# Schematic.net
KiCad netlist of a schematic drawn in Altium Designer
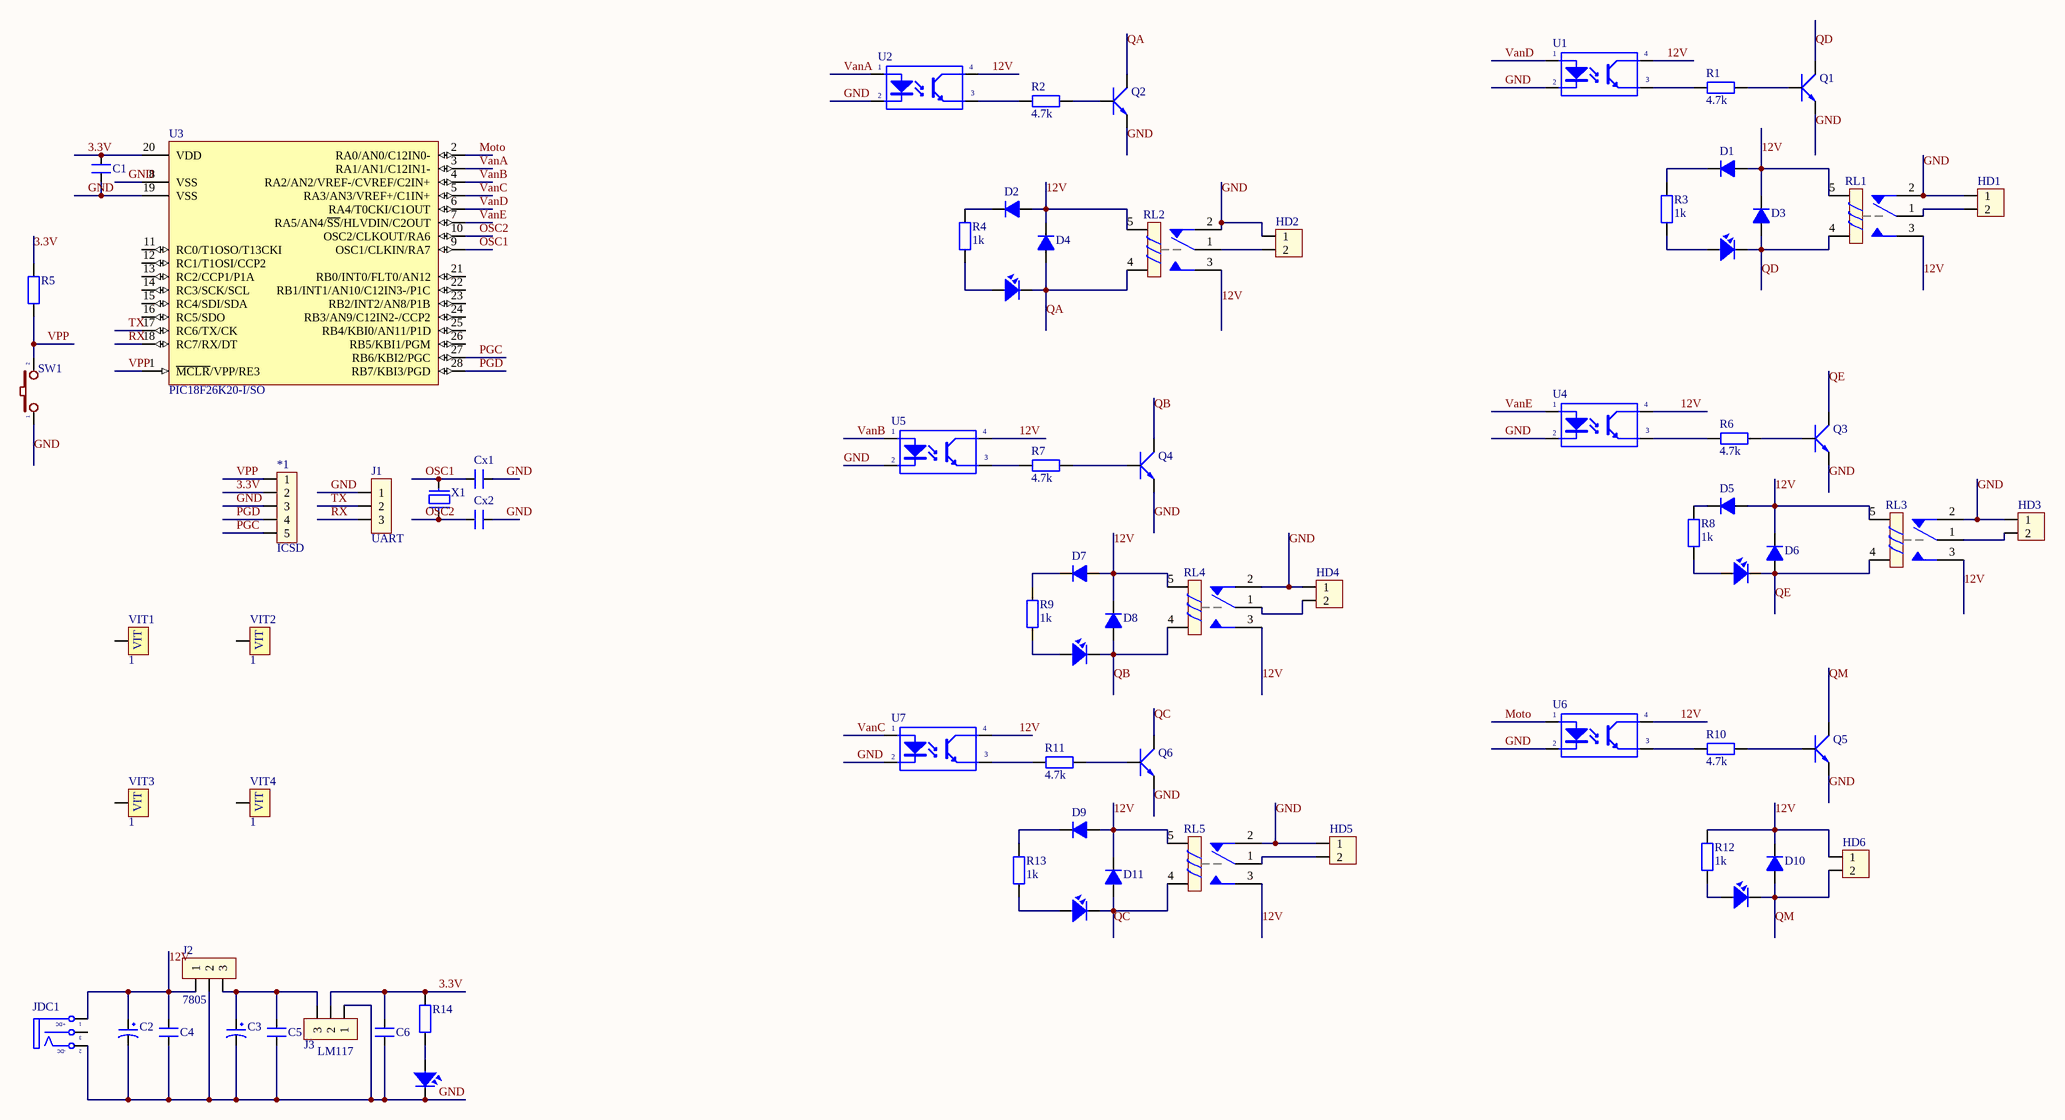
[diagram p0: Schematic.SchDoc]

(export (version "E")
  (design (tool "Eeschema 10.0.6"))
  (components
    (comp (ref "*1") (value "ICSD") (footprint "CON5") (libsource (lib "syhaunguyen") (part "JP5")))
    (comp (ref "C1")
      (value "104")
      (footprint "CN2")
      (description "Cap np Cremic Value  104pF => 105pF")
      (libsource (lib "syhaunguyen") (part "CN2"))
    )
    (comp (ref "C2")
      (value "100uF/35V")
      (footprint "CP1.5/3.4")
      (description "Cap 100uF/35V - 470uF/16V")
      (libsource (lib "syhaunguyen") (part "CP3"))
    )
    (comp (ref "C3")
      (value "10uF")
      (footprint "CP1/2")
      (description "Cap P  0,1uF < 22uF , 16 - 50V")
      (libsource (lib "syhaunguyen") (part "CP1"))
    )
    (comp (ref "C4")
      (value "104")
      (footprint "CN2")
      (description "Cap np Cremic Value  104pF => 105pF")
      (libsource (lib "syhaunguyen") (part "CN2"))
    )
    (comp (ref "C5")
      (value "104")
      (footprint "CN2")
      (description "Cap np Cremic Value  104pF => 105pF")
      (libsource (lib "syhaunguyen") (part "CN2"))
    )
    (comp (ref "C6")
      (value "104")
      (footprint "CN2")
      (description "Cap np Cremic Value  104pF => 105pF")
      (libsource (lib "syhaunguyen") (part "CN2"))
    )
    (comp (ref "Cx1")
      (value "33pF")
      (footprint "CN1")
      (description "Cap np Cremic value 1pF => 100pF")
      (libsource (lib "syhaunguyen") (part "CN0"))
    )
    (comp (ref "Cx2")
      (value "33pF")
      (footprint "CN1")
      (description "Cap np Cremic value 1pF => 100pF")
      (libsource (lib "syhaunguyen") (part "CN0"))
    )
    (comp (ref "D1")
      (value "1N4007")
      (footprint "D1A")
      (description "Diode 1A")
      (libsource (lib "syhaunguyen") (part "D1A"))
    )
    (comp (ref "D2")
      (value "1N4007")
      (footprint "D1A")
      (description "Diode 1A")
      (libsource (lib "syhaunguyen") (part "D1A"))
    )
    (comp (ref "D3")
      (value "1N4007")
      (footprint "D1A")
      (description "Diode 1A")
      (libsource (lib "syhaunguyen") (part "D1A"))
    )
    (comp (ref "D4")
      (value "1N4007")
      (footprint "D1A")
      (description "Diode 1A")
      (libsource (lib "syhaunguyen") (part "D1A"))
    )
    (comp (ref "D5")
      (value "1N4007")
      (footprint "D1A")
      (description "Diode 1A")
      (libsource (lib "syhaunguyen") (part "D1A"))
    )
    (comp (ref "D6")
      (value "1N4007")
      (footprint "D1A")
      (description "Diode 1A")
      (libsource (lib "syhaunguyen") (part "D1A"))
    )
    (comp (ref "D7")
      (value "1N4007")
      (footprint "D1A")
      (description "Diode 1A")
      (libsource (lib "syhaunguyen") (part "D1A"))
    )
    (comp (ref "D8")
      (value "1N4007")
      (footprint "D1A")
      (description "Diode 1A")
      (libsource (lib "syhaunguyen") (part "D1A"))
    )
    (comp (ref "D9")
      (value "1N4007")
      (footprint "D1A")
      (description "Diode 1A")
      (libsource (lib "syhaunguyen") (part "D1A"))
    )
    (comp (ref "D10")
      (value "1N4007")
      (footprint "D1A")
      (description "Diode 1A")
      (libsource (lib "syhaunguyen") (part "D1A"))
    )
    (comp (ref "D11")
      (value "1N4007")
      (footprint "D1A")
      (description "Diode 1A")
      (libsource (lib "syhaunguyen") (part "D1A"))
    )
    (comp (ref "HD1")
      (value "Header 2")
      (footprint "CON2")
      (description "Header 2 (Green)")
      (libsource (lib "syhaunguyen") (part "Hed2"))
    )
    (comp (ref "HD2")
      (value "Header 2")
      (footprint "CON2")
      (description "Header 2 (Green)")
      (libsource (lib "syhaunguyen") (part "Hed2"))
    )
    (comp (ref "HD3")
      (value "Header 2")
      (footprint "CON2")
      (description "Header 2 (Green)")
      (libsource (lib "syhaunguyen") (part "Hed2"))
    )
    (comp (ref "HD4")
      (value "Header 2")
      (footprint "CON2")
      (description "Header 2 (Green)")
      (libsource (lib "syhaunguyen") (part "Hed2"))
    )
    (comp (ref "HD5")
      (value "Header 2")
      (footprint "CON2")
      (description "Header 2 (Green)")
      (libsource (lib "syhaunguyen") (part "Hed2"))
    )
    (comp (ref "HD6")
      (value "Header 2")
      (footprint "CON2")
      (description "Header 2 (Green)")
      (libsource (lib "syhaunguyen") (part "Hed2"))
    )
    (comp (ref "J1")
      (value "UART")
      (footprint "CON3")
      (description "Jumper 3")
      (libsource (lib "") (part "JP3_1"))
    )
    (comp (ref "J2")
      (value "7805")
      (footprint "QTO-220H3")
      (description "Jumper 3")
      (libsource (lib "") (part "JP3_2"))
    )
    (comp (ref "J3")
      (value "LM117")
      (footprint "QTO-220H3")
      (description "Jumper 3")
      (libsource (lib "syhaunguyen") (part "JP3"))
    )
    (comp (ref "JDC1")
      (value "Jac DC")
      (footprint "DC-IN")
      (description "Jac DC input")
      (libsource (lib "syhaunguyen") (part "DCIN"))
    )
    (comp (ref "LED1")
      (value "LED")
      (footprint "LED-5TRED")
      (description "Led  Vuong")
      (libsource (lib "syhaunguyen") (part "LED"))
    )
    (comp (ref "LED2")
      (value "LED")
      (footprint "LED-5TRED")
      (description "Led  Vuong")
      (libsource (lib "syhaunguyen") (part "LED"))
    )
    (comp (ref "LED3")
      (value "LED")
      (footprint "LED-5TRED")
      (description "Led  Vuong")
      (libsource (lib "syhaunguyen") (part "LED"))
    )
    (comp (ref "LED4")
      (value "LED")
      (footprint "LED-5TRED")
      (description "Led  Vuong")
      (libsource (lib "syhaunguyen") (part "LED"))
    )
    (comp (ref "LED5")
      (value "LED")
      (footprint "LED-5TRED")
      (description "Led  Vuong")
      (libsource (lib "syhaunguyen") (part "LED"))
    )
    (comp (ref "LED6")
      (value "LED")
      (footprint "LED-5TRED")
      (description "Led  Vuong")
      (libsource (lib "syhaunguyen") (part "LED"))
    )
    (comp (ref "LED7")
      (value "LED")
      (footprint "LED-5TRED")
      (description "Led  Vuong")
      (libsource (lib "syhaunguyen") (part "LED"))
    )
    (comp (ref "Q1")
      (value "C1815")
      (footprint "QTO-92")
      (description "NPN 600mW, ECB")
      (libsource (lib "syhaunguyen") (part "C1815"))
    )
    (comp (ref "Q2")
      (value "C1815")
      (footprint "QTO-92")
      (description "NPN 600mW, ECB")
      (libsource (lib "syhaunguyen") (part "C1815"))
    )
    (comp (ref "Q3")
      (value "C1815")
      (footprint "QTO-92")
      (description "NPN 600mW, ECB")
      (libsource (lib "syhaunguyen") (part "C1815"))
    )
    (comp (ref "Q4")
      (value "C1815")
      (footprint "QTO-92")
      (description "NPN 600mW, ECB")
      (libsource (lib "syhaunguyen") (part "C1815"))
    )
    (comp (ref "Q5")
      (value "C1815")
      (footprint "QTO-92")
      (description "NPN 600mW, ECB")
      (libsource (lib "syhaunguyen") (part "C1815"))
    )
    (comp (ref "Q6")
      (value "C1815")
      (footprint "QTO-92")
      (description "NPN 600mW, ECB")
      (libsource (lib "syhaunguyen") (part "C1815"))
    )
    (comp (ref "R1")
      (value "4.7k")
      (footprint "R1/4W")
      (description "Resistor 1/4W")
      (libsource (lib "syhaunguyen") (part "R1/4W"))
    )
    (comp (ref "R2")
      (value "4.7k")
      (footprint "R1/4W")
      (description "Resistor 1/4W")
      (libsource (lib "syhaunguyen") (part "R1/4W"))
    )
    (comp (ref "R3")
      (value "1k")
      (footprint "R1/4W")
      (description "Resistor 1/4W")
      (libsource (lib "syhaunguyen") (part "R1/4W"))
    )
    (comp (ref "R4")
      (value "1k")
      (footprint "R1/4W")
      (description "Resistor 1/4W")
      (libsource (lib "syhaunguyen") (part "R1/4W"))
    )
    (comp (ref "R5")
      (value "1k")
      (footprint "R1/4W")
      (description "Resistor 1/4W")
      (libsource (lib "syhaunguyen") (part "R1/4W"))
    )
    (comp (ref "R6")
      (value "4.7k")
      (footprint "R1/4W")
      (description "Resistor 1/4W")
      (libsource (lib "syhaunguyen") (part "R1/4W"))
    )
    (comp (ref "R7")
      (value "4.7k")
      (footprint "R1/4W")
      (description "Resistor 1/4W")
      (libsource (lib "syhaunguyen") (part "R1/4W"))
    )
    (comp (ref "R8")
      (value "1k")
      (footprint "R1/4W")
      (description "Resistor 1/4W")
      (libsource (lib "syhaunguyen") (part "R1/4W"))
    )
    (comp (ref "R9")
      (value "1k")
      (footprint "R1/4W")
      (description "Resistor 1/4W")
      (libsource (lib "syhaunguyen") (part "R1/4W"))
    )
    (comp (ref "R10")
      (value "4.7k")
      (footprint "R1/4W")
      (description "Resistor 1/4W")
      (libsource (lib "syhaunguyen") (part "R1/4W"))
    )
    (comp (ref "R11")
      (value "4.7k")
      (footprint "R1/4W")
      (description "Resistor 1/4W")
      (libsource (lib "syhaunguyen") (part "R1/4W"))
    )
    (comp (ref "R12")
      (value "1k")
      (footprint "R1/4W")
      (description "Resistor 1/4W")
      (libsource (lib "syhaunguyen") (part "R1/4W"))
    )
    (comp (ref "R13")
      (value "1k")
      (footprint "R1/4W")
      (description "Resistor 1/4W")
      (libsource (lib "syhaunguyen") (part "R1/4W"))
    )
    (comp (ref "R14")
      (value "1k")
      (footprint "R1/4W")
      (description "Resistor 1/4W")
      (libsource (lib "syhaunguyen") (part "R1/4W"))
    )
    (comp (ref "RL1")
      (value "Relay 10A/12V")
      (footprint "RL_SPDT_10A")
      (description "Relay SPDT,10A - 12VDC 5 Pin")
      (libsource (lib "syhaunguyen") (part "Relay 1"))
    )
    (comp (ref "RL2")
      (value "Relay 10A/12V")
      (footprint "RL_SPDT_10A")
      (description "Relay SPDT,10A - 12VDC 5 Pin")
      (libsource (lib "syhaunguyen") (part "Relay 1"))
    )
    (comp (ref "RL3")
      (value "Relay 10A/12V")
      (footprint "RL_SPDT_10A")
      (description "Relay SPDT,10A - 12VDC 5 Pin")
      (libsource (lib "syhaunguyen") (part "Relay 1"))
    )
    (comp (ref "RL4")
      (value "Relay 10A/12V")
      (footprint "RL_SPDT_10A")
      (description "Relay SPDT,10A - 12VDC 5 Pin")
      (libsource (lib "syhaunguyen") (part "Relay 1"))
    )
    (comp (ref "RL5")
      (value "Relay 10A/12V")
      (footprint "RL_SPDT_10A")
      (description "Relay SPDT,10A - 12VDC 5 Pin")
      (libsource (lib "syhaunguyen") (part "Relay 1"))
    )
    (comp (ref "SW1")
      (value "SW")
      (footprint "SW2")
      (description "Switch button 2 pin")
      (libsource (lib "syhaunguyen") (part "SW2"))
    )
    (comp (ref "U1")
      (value "PC817")
      (footprint "DIP4/W0.3")
      (description "Single Opto")
      (libsource (lib "syhaunguyen") (part "PC817"))
    )
    (comp (ref "U2")
      (value "PC817")
      (footprint "DIP4/W0.3")
      (description "Single Opto")
      (libsource (lib "syhaunguyen") (part "PC817"))
    )
    (comp (ref "U3")
      (value "PIC18F26K20-I/SO")
      (footprint "SOIC-SO28_N")
      (fields (field (name "PUBLISHER") "Altium Limited"))
      (libsource (lib "Microchip Microcontroller 8-Bit PIC18") (part "PIC18F26K20-I/SO"))
    )
    (comp (ref "U4")
      (value "PC817")
      (footprint "DIP4/W0.3")
      (description "Single Opto")
      (libsource (lib "syhaunguyen") (part "PC817"))
    )
    (comp (ref "U5")
      (value "PC817")
      (footprint "DIP4/W0.3")
      (description "Single Opto")
      (libsource (lib "syhaunguyen") (part "PC817"))
    )
    (comp (ref "U6")
      (value "PC817")
      (footprint "DIP4/W0.3")
      (description "Single Opto")
      (libsource (lib "syhaunguyen") (part "PC817"))
    )
    (comp (ref "U7")
      (value "PC817")
      (footprint "DIP4/W0.3")
      (description "Single Opto")
      (libsource (lib "syhaunguyen") (part "PC817"))
    )
    (comp (ref "VIT1")
      (value "1")
      (footprint "VIT")
      (description "Oc Vit")
      (libsource (lib "syhaunguyen") (part "VIT"))
    )
    (comp (ref "VIT2")
      (value "1")
      (footprint "VIT")
      (description "Oc Vit")
      (libsource (lib "syhaunguyen") (part "VIT"))
    )
    (comp (ref "VIT3")
      (value "1")
      (footprint "VIT")
      (description "Oc Vit")
      (libsource (lib "syhaunguyen") (part "VIT"))
    )
    (comp (ref "VIT4")
      (value "1")
      (footprint "VIT")
      (description "Oc Vit")
      (libsource (lib "syhaunguyen") (part "VIT"))
    )
    (comp (ref "X1")
      (value "4Mhz")
      (footprint "XT2")
      (description "Crystal For all Crystal 2pin.")
      (libsource (lib "syhaunguyen") (part "XT2"))
    )
  )
  (nets
    (net (code "1") (name "/3.3V") (class "Default")
      (node (ref "*1") (pin "2") (pinfunction "2_2") (pintype "passive"))
      (node (ref "C1") (pin "2") (pinfunction "2_2") (pintype "passive"))
      (node (ref "C6") (pin "1") (pinfunction "1_1") (pintype "passive"))
      (node (ref "J3") (pin "2") (pinfunction "2_2") (pintype "passive"))
      (node (ref "R14") (pin "2") (pinfunction "2_2") (pintype "passive"))
      (node (ref "R5") (pin "2") (pinfunction "2_2") (pintype "passive"))
      (node (ref "U3") (pin "20") (pinfunction "VDD_20") (pintype "power_in"))
    )
    (net (code "2") (name "/12V") (class "Default")
      (node (ref "C2") (pin "1") (pinfunction "1_1") (pintype "passive"))
      (node (ref "C4") (pin "1") (pinfunction "1_1") (pintype "passive"))
      (node (ref "D1") (pin "1") (pinfunction "A_1") (pintype "passive"))
      (node (ref "D10") (pin "2") (pinfunction "K_2") (pintype "passive"))
      (node (ref "D11") (pin "2") (pinfunction "K_2") (pintype "passive"))
      (node (ref "D2") (pin "1") (pinfunction "A_1") (pintype "passive"))
      (node (ref "D3") (pin "2") (pinfunction "K_2") (pintype "passive"))
      (node (ref "D4") (pin "2") (pinfunction "K_2") (pintype "passive"))
      (node (ref "D5") (pin "1") (pinfunction "A_1") (pintype "passive"))
      (node (ref "D6") (pin "2") (pinfunction "K_2") (pintype "passive"))
      (node (ref "D7") (pin "1") (pinfunction "A_1") (pintype "passive"))
      (node (ref "D8") (pin "2") (pinfunction "K_2") (pintype "passive"))
      (node (ref "D9") (pin "1") (pinfunction "A_1") (pintype "passive"))
      (node (ref "HD6") (pin "1") (pinfunction "1_1") (pintype "passive"))
      (node (ref "J2") (pin "1") (pinfunction "1_1") (pintype "passive"))
      (node (ref "JDC1") (pin "1") (pinfunction "T_1") (pintype "passive"))
      (node (ref "R12") (pin "2") (pinfunction "2_2") (pintype "passive"))
      (node (ref "RL1") (pin "3") (pinfunction "3_3") (pintype "passive"))
      (node (ref "RL1") (pin "5") (pinfunction "5_5") (pintype "passive"))
      (node (ref "RL2") (pin "3") (pinfunction "3_3") (pintype "passive"))
      (node (ref "RL2") (pin "5") (pinfunction "5_5") (pintype "passive"))
      (node (ref "RL3") (pin "3") (pinfunction "3_3") (pintype "passive"))
      (node (ref "RL3") (pin "5") (pinfunction "5_5") (pintype "passive"))
      (node (ref "RL4") (pin "3") (pinfunction "3_3") (pintype "passive"))
      (node (ref "RL4") (pin "5") (pinfunction "5_5") (pintype "passive"))
      (node (ref "RL5") (pin "3") (pinfunction "3_3") (pintype "passive"))
      (node (ref "RL5") (pin "5") (pinfunction "5_5") (pintype "passive"))
      (node (ref "U1") (pin "4") (pinfunction "C_4") (pintype "passive"))
      (node (ref "U2") (pin "4") (pinfunction "C_4") (pintype "passive"))
      (node (ref "U4") (pin "4") (pinfunction "C_4") (pintype "passive"))
      (node (ref "U5") (pin "4") (pinfunction "C_4") (pintype "passive"))
      (node (ref "U6") (pin "4") (pinfunction "C_4") (pintype "passive"))
      (node (ref "U7") (pin "4") (pinfunction "C_4") (pintype "passive"))
    )
    (net (code "3") (name "/GND") (class "Default")
      (node (ref "*1") (pin "3") (pinfunction "3_3") (pintype "passive"))
      (node (ref "C1") (pin "1") (pinfunction "1_1") (pintype "passive"))
      (node (ref "C2") (pin "2") (pinfunction "2_2") (pintype "passive"))
      (node (ref "C3") (pin "2") (pinfunction "2_2") (pintype "passive"))
      (node (ref "C4") (pin "2") (pinfunction "2_2") (pintype "passive"))
      (node (ref "C5") (pin "2") (pinfunction "2_2") (pintype "passive"))
      (node (ref "C6") (pin "2") (pinfunction "2_2") (pintype "passive"))
      (node (ref "Cx1") (pin "2") (pinfunction "2_2") (pintype "passive"))
      (node (ref "Cx2") (pin "2") (pinfunction "2_2") (pintype "passive"))
      (node (ref "HD1") (pin "1") (pinfunction "1_1") (pintype "passive"))
      (node (ref "HD2") (pin "1") (pinfunction "1_1") (pintype "passive"))
      (node (ref "HD3") (pin "1") (pinfunction "1_1") (pintype "passive"))
      (node (ref "HD4") (pin "1") (pinfunction "1_1") (pintype "passive"))
      (node (ref "HD5") (pin "1") (pinfunction "1_1") (pintype "passive"))
      (node (ref "J1") (pin "1") (pinfunction "1_1") (pintype "passive"))
      (node (ref "J2") (pin "2") (pinfunction "2_2") (pintype "passive"))
      (node (ref "J3") (pin "1") (pinfunction "1_1") (pintype "passive"))
      (node (ref "JDC1") (pin "2") (pinfunction "TN_2") (pintype "passive"))
      (node (ref "LED7") (pin "2") (pinfunction "2_2") (pintype "passive"))
      (node (ref "Q1") (pin "1") (pinfunction "E_1") (pintype "passive"))
      (node (ref "Q2") (pin "1") (pinfunction "E_1") (pintype "passive"))
      (node (ref "Q3") (pin "1") (pinfunction "E_1") (pintype "passive"))
      (node (ref "Q4") (pin "1") (pinfunction "E_1") (pintype "passive"))
      (node (ref "Q5") (pin "1") (pinfunction "E_1") (pintype "passive"))
      (node (ref "Q6") (pin "1") (pinfunction "E_1") (pintype "passive"))
      (node (ref "RL1") (pin "2") (pinfunction "2_2") (pintype "passive"))
      (node (ref "RL2") (pin "2") (pinfunction "2_2") (pintype "passive"))
      (node (ref "RL3") (pin "2") (pinfunction "2_2") (pintype "passive"))
      (node (ref "RL4") (pin "2") (pinfunction "2_2") (pintype "passive"))
      (node (ref "RL5") (pin "2") (pinfunction "2_2") (pintype "passive"))
      (node (ref "SW1") (pin "1") (pinfunction "1_1") (pintype "passive"))
      (node (ref "U1") (pin "2") (pinfunction "K_2") (pintype "passive"))
      (node (ref "U2") (pin "2") (pinfunction "K_2") (pintype "passive"))
      (node (ref "U3") (pin "19") (pinfunction "VSS_19") (pintype "power_in"))
      (node (ref "U3") (pin "8") (pinfunction "VSS_8") (pintype "power_in"))
      (node (ref "U4") (pin "2") (pinfunction "K_2") (pintype "passive"))
      (node (ref "U5") (pin "2") (pinfunction "K_2") (pintype "passive"))
      (node (ref "U6") (pin "2") (pinfunction "K_2") (pintype "passive"))
      (node (ref "U7") (pin "2") (pinfunction "K_2") (pintype "passive"))
    )
    (net (code "4") (name "/Moto") (class "Default")
      (node (ref "U3") (pin "2") (pinfunction "RA0/AN0/C12IN0-_2") (pintype "bidirectional"))
      (node (ref "U6") (pin "1") (pinfunction "A_1") (pintype "passive"))
    )
    (net (code "5") (name "/OSC1") (class "Default")
      (node (ref "Cx1") (pin "1") (pinfunction "1_1") (pintype "passive"))
      (node (ref "U3") (pin "9") (pinfunction "OSC1/CLKIN/RA7_9") (pintype "bidirectional"))
      (node (ref "X1") (pin "2") (pinfunction "2_2") (pintype "passive"))
    )
    (net (code "6") (name "/OSC2") (class "Default")
      (node (ref "Cx2") (pin "1") (pinfunction "1_1") (pintype "passive"))
      (node (ref "U3") (pin "10") (pinfunction "OSC2/CLKOUT/RA6_10") (pintype "bidirectional"))
      (node (ref "X1") (pin "1") (pinfunction "1_1") (pintype "passive"))
    )
    (net (code "7") (name "/PGC") (class "Default")
      (node (ref "*1") (pin "5") (pinfunction "5_5") (pintype "passive"))
      (node (ref "U3") (pin "27") (pinfunction "RB6/KBI2/PGC_27") (pintype "bidirectional"))
    )
    (net (code "8") (name "/PGD") (class "Default")
      (node (ref "*1") (pin "4") (pinfunction "4_4") (pintype "passive"))
      (node (ref "U3") (pin "28") (pinfunction "RB7/KBI3/PGD_28") (pintype "bidirectional"))
    )
    (net (code "9") (name "/QA") (class "Default")
      (node (ref "D4") (pin "1") (pinfunction "A_1") (pintype "passive"))
      (node (ref "LED2") (pin "2") (pinfunction "2_2") (pintype "passive"))
      (node (ref "Q2") (pin "2") (pinfunction "C_2") (pintype "passive"))
      (node (ref "RL2") (pin "4") (pinfunction "4_4") (pintype "passive"))
    )
    (net (code "10") (name "/QB") (class "Default")
      (node (ref "D8") (pin "1") (pinfunction "A_1") (pintype "passive"))
      (node (ref "LED4") (pin "2") (pinfunction "2_2") (pintype "passive"))
      (node (ref "Q4") (pin "2") (pinfunction "C_2") (pintype "passive"))
      (node (ref "RL4") (pin "4") (pinfunction "4_4") (pintype "passive"))
    )
    (net (code "11") (name "/QC") (class "Default")
      (node (ref "D11") (pin "1") (pinfunction "A_1") (pintype "passive"))
      (node (ref "LED6") (pin "2") (pinfunction "2_2") (pintype "passive"))
      (node (ref "Q6") (pin "2") (pinfunction "C_2") (pintype "passive"))
      (node (ref "RL5") (pin "4") (pinfunction "4_4") (pintype "passive"))
    )
    (net (code "12") (name "/QD") (class "Default")
      (node (ref "D3") (pin "1") (pinfunction "A_1") (pintype "passive"))
      (node (ref "LED1") (pin "2") (pinfunction "2_2") (pintype "passive"))
      (node (ref "Q1") (pin "2") (pinfunction "C_2") (pintype "passive"))
      (node (ref "RL1") (pin "4") (pinfunction "4_4") (pintype "passive"))
    )
    (net (code "13") (name "/QE") (class "Default")
      (node (ref "D6") (pin "1") (pinfunction "A_1") (pintype "passive"))
      (node (ref "LED3") (pin "2") (pinfunction "2_2") (pintype "passive"))
      (node (ref "Q3") (pin "2") (pinfunction "C_2") (pintype "passive"))
      (node (ref "RL3") (pin "4") (pinfunction "4_4") (pintype "passive"))
    )
    (net (code "14") (name "/QM") (class "Default")
      (node (ref "D10") (pin "1") (pinfunction "A_1") (pintype "passive"))
      (node (ref "HD6") (pin "2") (pinfunction "2_2") (pintype "passive"))
      (node (ref "LED5") (pin "2") (pinfunction "2_2") (pintype "passive"))
      (node (ref "Q5") (pin "2") (pinfunction "C_2") (pintype "passive"))
    )
    (net (code "15") (name "/RX") (class "Default")
      (node (ref "J1") (pin "3") (pinfunction "3_3") (pintype "passive"))
      (node (ref "U3") (pin "18") (pinfunction "RC7/RX/DT_18") (pintype "bidirectional"))
    )
    (net (code "16") (name "/TX") (class "Default")
      (node (ref "J1") (pin "2") (pinfunction "2_2") (pintype "passive"))
      (node (ref "U3") (pin "17") (pinfunction "RC6/TX/CK_17") (pintype "bidirectional"))
    )
    (net (code "17") (name "/VPP") (class "Default")
      (node (ref "*1") (pin "1") (pinfunction "1_1") (pintype "passive"))
      (node (ref "R5") (pin "1") (pinfunction "1_1") (pintype "passive"))
      (node (ref "SW1") (pin "2") (pinfunction "2_2") (pintype "passive"))
      (node (ref "U3") (pin "1") (pinfunction "~{MCLR}/VPP/RE3_1") (pintype "input"))
    )
    (net (code "18") (name "/VanA") (class "Default")
      (node (ref "U2") (pin "1") (pinfunction "A_1") (pintype "passive"))
      (node (ref "U3") (pin "3") (pinfunction "RA1/AN1/C12IN1-_3") (pintype "bidirectional"))
    )
    (net (code "19") (name "/VanB") (class "Default")
      (node (ref "U3") (pin "4") (pinfunction "RA2/AN2/VREF-/CVREF/C2IN+_4") (pintype "bidirectional"))
      (node (ref "U5") (pin "1") (pinfunction "A_1") (pintype "passive"))
    )
    (net (code "20") (name "/VanC") (class "Default")
      (node (ref "U3") (pin "5") (pinfunction "RA3/AN3/VREF+/C1IN+_5") (pintype "bidirectional"))
      (node (ref "U7") (pin "1") (pinfunction "A_1") (pintype "passive"))
    )
    (net (code "21") (name "/VanD") (class "Default")
      (node (ref "U1") (pin "1") (pinfunction "A_1") (pintype "passive"))
      (node (ref "U3") (pin "6") (pinfunction "RA4/T0CKI/C1OUT_6") (pintype "bidirectional"))
    )
    (net (code "22") (name "/VanE") (class "Default")
      (node (ref "U3") (pin "7") (pinfunction "RA5/AN4/~{SS}/HLVDIN/C2OUT_7") (pintype "bidirectional"))
      (node (ref "U4") (pin "1") (pinfunction "A_1") (pintype "passive"))
    )
    (net (code "23") (name "Net-(C3-Pad1)") (class "Default")
      (node (ref "C3") (pin "1") (pinfunction "1_1") (pintype "passive"))
      (node (ref "C5") (pin "1") (pinfunction "1_1") (pintype "passive"))
      (node (ref "J2") (pin "3") (pinfunction "3_3") (pintype "passive"))
      (node (ref "J3") (pin "3") (pinfunction "3_3") (pintype "passive"))
    )
    (net (code "24") (name "Net-(D1-K)") (class "Default")
      (node (ref "D1") (pin "2") (pinfunction "K_2") (pintype "passive"))
      (node (ref "R3") (pin "2") (pinfunction "2_2") (pintype "passive"))
    )
    (net (code "25") (name "Net-(D2-K)") (class "Default")
      (node (ref "D2") (pin "2") (pinfunction "K_2") (pintype "passive"))
      (node (ref "R4") (pin "2") (pinfunction "2_2") (pintype "passive"))
    )
    (net (code "26") (name "Net-(D5-K)") (class "Default")
      (node (ref "D5") (pin "2") (pinfunction "K_2") (pintype "passive"))
      (node (ref "R8") (pin "2") (pinfunction "2_2") (pintype "passive"))
    )
    (net (code "27") (name "Net-(D7-K)") (class "Default")
      (node (ref "D7") (pin "2") (pinfunction "K_2") (pintype "passive"))
      (node (ref "R9") (pin "2") (pinfunction "2_2") (pintype "passive"))
    )
    (net (code "28") (name "Net-(D9-K)") (class "Default")
      (node (ref "D9") (pin "2") (pinfunction "K_2") (pintype "passive"))
      (node (ref "R13") (pin "2") (pinfunction "2_2") (pintype "passive"))
    )
    (net (code "29") (name "Net-(HD1-Pad2)") (class "Default")
      (node (ref "HD1") (pin "2") (pinfunction "2_2") (pintype "passive"))
      (node (ref "RL1") (pin "1") (pinfunction "1_1") (pintype "passive"))
    )
    (net (code "30") (name "Net-(HD2-Pad2)") (class "Default")
      (node (ref "HD2") (pin "2") (pinfunction "2_2") (pintype "passive"))
      (node (ref "RL2") (pin "1") (pinfunction "1_1") (pintype "passive"))
    )
    (net (code "31") (name "Net-(HD3-Pad2)") (class "Default")
      (node (ref "HD3") (pin "2") (pinfunction "2_2") (pintype "passive"))
      (node (ref "RL3") (pin "1") (pinfunction "1_1") (pintype "passive"))
    )
    (net (code "32") (name "Net-(HD4-Pad2)") (class "Default")
      (node (ref "HD4") (pin "2") (pinfunction "2_2") (pintype "passive"))
      (node (ref "RL4") (pin "1") (pinfunction "1_1") (pintype "passive"))
    )
    (net (code "33") (name "Net-(HD5-Pad2)") (class "Default")
      (node (ref "HD5") (pin "2") (pinfunction "2_2") (pintype "passive"))
      (node (ref "RL5") (pin "1") (pinfunction "1_1") (pintype "passive"))
    )
    (net (code "34") (name "Net-(LED1-Pad1)") (class "Default")
      (node (ref "LED1") (pin "1") (pinfunction "1_1") (pintype "passive"))
      (node (ref "R3") (pin "1") (pinfunction "1_1") (pintype "passive"))
    )
    (net (code "35") (name "Net-(LED2-Pad1)") (class "Default")
      (node (ref "LED2") (pin "1") (pinfunction "1_1") (pintype "passive"))
      (node (ref "R4") (pin "1") (pinfunction "1_1") (pintype "passive"))
    )
    (net (code "36") (name "Net-(LED3-Pad1)") (class "Default")
      (node (ref "LED3") (pin "1") (pinfunction "1_1") (pintype "passive"))
      (node (ref "R8") (pin "1") (pinfunction "1_1") (pintype "passive"))
    )
    (net (code "37") (name "Net-(LED4-Pad1)") (class "Default")
      (node (ref "LED4") (pin "1") (pinfunction "1_1") (pintype "passive"))
      (node (ref "R9") (pin "1") (pinfunction "1_1") (pintype "passive"))
    )
    (net (code "38") (name "Net-(LED5-Pad1)") (class "Default")
      (node (ref "LED5") (pin "1") (pinfunction "1_1") (pintype "passive"))
      (node (ref "R12") (pin "1") (pinfunction "1_1") (pintype "passive"))
    )
    (net (code "39") (name "Net-(LED6-Pad1)") (class "Default")
      (node (ref "LED6") (pin "1") (pinfunction "1_1") (pintype "passive"))
      (node (ref "R13") (pin "1") (pinfunction "1_1") (pintype "passive"))
    )
    (net (code "40") (name "Net-(LED7-Pad1)") (class "Default")
      (node (ref "LED7") (pin "1") (pinfunction "1_1") (pintype "passive"))
      (node (ref "R14") (pin "1") (pinfunction "1_1") (pintype "passive"))
    )
    (net (code "41") (name "Net-(Q1-B)") (class "Default")
      (node (ref "Q1") (pin "3") (pinfunction "B_3") (pintype "passive"))
      (node (ref "R1") (pin "2") (pinfunction "2_2") (pintype "passive"))
    )
    (net (code "42") (name "Net-(Q2-B)") (class "Default")
      (node (ref "Q2") (pin "3") (pinfunction "B_3") (pintype "passive"))
      (node (ref "R2") (pin "2") (pinfunction "2_2") (pintype "passive"))
    )
    (net (code "43") (name "Net-(Q3-B)") (class "Default")
      (node (ref "Q3") (pin "3") (pinfunction "B_3") (pintype "passive"))
      (node (ref "R6") (pin "2") (pinfunction "2_2") (pintype "passive"))
    )
    (net (code "44") (name "Net-(Q4-B)") (class "Default")
      (node (ref "Q4") (pin "3") (pinfunction "B_3") (pintype "passive"))
      (node (ref "R7") (pin "2") (pinfunction "2_2") (pintype "passive"))
    )
    (net (code "45") (name "Net-(Q5-B)") (class "Default")
      (node (ref "Q5") (pin "3") (pinfunction "B_3") (pintype "passive"))
      (node (ref "R10") (pin "2") (pinfunction "2_2") (pintype "passive"))
    )
    (net (code "46") (name "Net-(Q6-B)") (class "Default")
      (node (ref "Q6") (pin "3") (pinfunction "B_3") (pintype "passive"))
      (node (ref "R11") (pin "2") (pinfunction "2_2") (pintype "passive"))
    )
    (net (code "47") (name "Net-(U1-E)") (class "Default")
      (node (ref "R1") (pin "1") (pinfunction "1_1") (pintype "passive"))
      (node (ref "U1") (pin "3") (pinfunction "E_3") (pintype "passive"))
    )
    (net (code "48") (name "Net-(U2-E)") (class "Default")
      (node (ref "R2") (pin "1") (pinfunction "1_1") (pintype "passive"))
      (node (ref "U2") (pin "3") (pinfunction "E_3") (pintype "passive"))
    )
    (net (code "49") (name "Net-(U4-E)") (class "Default")
      (node (ref "R6") (pin "1") (pinfunction "1_1") (pintype "passive"))
      (node (ref "U4") (pin "3") (pinfunction "E_3") (pintype "passive"))
    )
    (net (code "50") (name "Net-(U5-E)") (class "Default")
      (node (ref "R7") (pin "1") (pinfunction "1_1") (pintype "passive"))
      (node (ref "U5") (pin "3") (pinfunction "E_3") (pintype "passive"))
    )
    (net (code "51") (name "Net-(U6-E)") (class "Default")
      (node (ref "R10") (pin "1") (pinfunction "1_1") (pintype "passive"))
      (node (ref "U6") (pin "3") (pinfunction "E_3") (pintype "passive"))
    )
    (net (code "52") (name "Net-(U7-E)") (class "Default")
      (node (ref "R11") (pin "1") (pinfunction "1_1") (pintype "passive"))
      (node (ref "U7") (pin "3") (pinfunction "E_3") (pintype "passive"))
    )
    (net (code "53") (name "unconnected-(JDC1-S-Pad3)") (class "Default")
      (node (ref "JDC1") (pin "3") (pinfunction "S_3") (pintype "power_in"))
    )
    (net (code "54") (name "unconnected-(U3-RB0{slash}INT0{slash}FLT0{slash}AN12-Pad21)") (class "Default")
      (node (ref "U3") (pin "21") (pinfunction "RB0/INT0/FLT0/AN12_21") (pintype "bidirectional"))
    )
    (net (code "55") (name "unconnected-(U3-RB1{slash}INT1{slash}AN10{slash}C12IN3-{slash}P1C-Pad22)") (class "Default")
      (node (ref "U3") (pin "22") (pinfunction "RB1/INT1/AN10/C12IN3-/P1C_22") (pintype "bidirectional"))
    )
    (net (code "56") (name "unconnected-(U3-RB2{slash}INT2{slash}AN8{slash}P1B-Pad23)") (class "Default")
      (node (ref "U3") (pin "23") (pinfunction "RB2/INT2/AN8/P1B_23") (pintype "bidirectional"))
    )
    (net (code "57") (name "unconnected-(U3-RB3{slash}AN9{slash}C12IN2-{slash}CCP2-Pad24)") (class "Default")
      (node (ref "U3") (pin "24") (pinfunction "RB3/AN9/C12IN2-/CCP2_24") (pintype "bidirectional"))
    )
    (net (code "58") (name "unconnected-(U3-RB4{slash}KBI0{slash}AN11{slash}P1D-Pad25)") (class "Default")
      (node (ref "U3") (pin "25") (pinfunction "RB4/KBI0/AN11/P1D_25") (pintype "bidirectional"))
    )
    (net (code "59") (name "unconnected-(U3-RB5{slash}KBI1{slash}PGM-Pad26)") (class "Default")
      (node (ref "U3") (pin "26") (pinfunction "RB5/KBI1/PGM_26") (pintype "bidirectional"))
    )
    (net (code "60") (name "unconnected-(U3-RC0{slash}T1OSO{slash}T13CKI-Pad11)") (class "Default")
      (node (ref "U3") (pin "11") (pinfunction "RC0/T1OSO/T13CKI_11") (pintype "bidirectional"))
    )
    (net (code "61") (name "unconnected-(U3-RC1{slash}T1OSI{slash}CCP2-Pad12)") (class "Default")
      (node (ref "U3") (pin "12") (pinfunction "RC1/T1OSI/CCP2_12") (pintype "bidirectional"))
    )
    (net (code "62") (name "unconnected-(U3-RC2{slash}CCP1{slash}P1A-Pad13)") (class "Default")
      (node (ref "U3") (pin "13") (pinfunction "RC2/CCP1/P1A_13") (pintype "bidirectional"))
    )
    (net (code "63") (name "unconnected-(U3-RC3{slash}SCK{slash}SCL-Pad14)") (class "Default")
      (node (ref "U3") (pin "14") (pinfunction "RC3/SCK/SCL_14") (pintype "bidirectional"))
    )
    (net (code "64") (name "unconnected-(U3-RC4{slash}SDI{slash}SDA-Pad15)") (class "Default")
      (node (ref "U3") (pin "15") (pinfunction "RC4/SDI/SDA_15") (pintype "bidirectional"))
    )
    (net (code "65") (name "unconnected-(U3-RC5{slash}SDO-Pad16)") (class "Default")
      (node (ref "U3") (pin "16") (pinfunction "RC5/SDO_16") (pintype "bidirectional"))
    )
    (net (code "66") (name "unconnected-(VIT1-1-PadVIT1)") (class "Default")
      (node (ref "VIT1") (pin "VIT1") (pinfunction "1_VIT1") (pintype "passive"))
    )
    (net (code "67") (name "unconnected-(VIT2-1-PadVIT1)") (class "Default")
      (node (ref "VIT2") (pin "VIT1") (pinfunction "1_VIT1") (pintype "passive"))
    )
    (net (code "68") (name "unconnected-(VIT3-1-PadVIT1)") (class "Default")
      (node (ref "VIT3") (pin "VIT1") (pinfunction "1_VIT1") (pintype "passive"))
    )
    (net (code "69") (name "unconnected-(VIT4-1-PadVIT1)") (class "Default")
      (node (ref "VIT4") (pin "VIT1") (pinfunction "1_VIT1") (pintype "passive"))
    )
  )
)
